# bootloader1.net
KiCad netlist of a schematic drawn in EAGLE
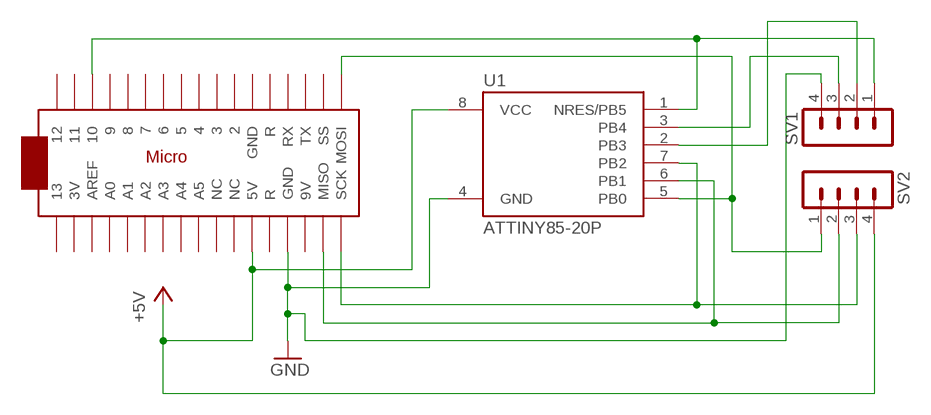
[diagram p0: schematic, sheet 1]

(export (version "E")
  (design (tool "Eeschema 10.0.6"))
  (components
    (comp (ref "SV1")
      (value "PINHEAD-MA04-1")
      (footprint "eagle-import:PINHEAD-MA04-1")
      (libsource (lib "eagle-import") (part "PINHEAD-MA04-1"))
    )
    (comp (ref "SV2")
      (value "PINHEAD-MA04-1")
      (footprint "eagle-import:PINHEAD-MA04-1")
      (libsource (lib "eagle-import") (part "PINHEAD-MA04-1"))
    )
    (comp (ref "U$1")
      (value "ARDUINOMICRO")
      (footprint "eagle-import:ARDUINOMICRO")
      (libsource (lib "eagle-import") (part "ARDUINOMICRO"))
    )
    (comp (ref "U1")
      (value "ATTINY85-20P")
      (footprint "eagle-import:PDIP08_300MIL")
      (libsource (lib "eagle-import") (part "ATTINY85P-20"))
    )
  )
  (nets
    (net (code "1") (name "+5V") (class "Default")
      (node (ref "SV2") (pin "4") (pinfunction "4_4") (pintype "passive"))
      (node (ref "U$1") (pin "P$23") (pinfunction "5V_P$23") (pintype "bidirectional"))
      (node (ref "U1") (pin "8") (pinfunction "VCC_8") (pintype "power_in"))
    )
    (net (code "2") (name "GND") (class "Default")
      (node (ref "SV1") (pin "4") (pinfunction "4_4") (pintype "passive"))
      (node (ref "U$1") (pin "P$12") (pinfunction "GND_P$12") (pintype "bidirectional"))
      (node (ref "U1") (pin "4") (pinfunction "GND_4") (pintype "power_in"))
    )
    (net (code "3") (name "Net-(U$1-10)") (class "Default")
      (node (ref "SV1") (pin "1") (pinfunction "1_1") (pintype "passive"))
      (node (ref "U$1") (pin "P$3") (pinfunction "10_P$3") (pintype "bidirectional"))
      (node (ref "U1") (pin "1") (pinfunction "NRES/PB5_1") (pintype "bidirectional"))
    )
    (net (code "4") (name "Net-(U$1-MISO)") (class "Default")
      (node (ref "SV2") (pin "2") (pinfunction "2_2") (pintype "passive"))
      (node (ref "U$1") (pin "P$19") (pinfunction "MISO_P$19") (pintype "bidirectional"))
      (node (ref "U1") (pin "6") (pinfunction "PB1_6") (pintype "bidirectional"))
    )
    (net (code "5") (name "Net-(U$1-MOSI)") (class "Default")
      (node (ref "SV2") (pin "1") (pinfunction "1_1") (pintype "passive"))
      (node (ref "U$1") (pin "P$17") (pinfunction "MOSI_P$17") (pintype "bidirectional"))
      (node (ref "U1") (pin "5") (pinfunction "PB0_5") (pintype "bidirectional"))
    )
    (net (code "6") (name "Net-(U$1-SCK)") (class "Default")
      (node (ref "SV2") (pin "3") (pinfunction "3_3") (pintype "passive"))
      (node (ref "U$1") (pin "P$18") (pinfunction "SCK_P$18") (pintype "bidirectional"))
      (node (ref "U1") (pin "7") (pinfunction "PB2_7") (pintype "bidirectional"))
    )
    (net (code "7") (name "Net-(U1-PB3)") (class "Default")
      (node (ref "SV1") (pin "2") (pinfunction "2_2") (pintype "passive"))
      (node (ref "U1") (pin "2") (pinfunction "PB3_2") (pintype "bidirectional"))
    )
    (net (code "8") (name "Net-(U1-PB4)") (class "Default")
      (node (ref "SV1") (pin "3") (pinfunction "3_3") (pintype "passive"))
      (node (ref "U1") (pin "3") (pinfunction "PB4_3") (pintype "bidirectional"))
    )
    (net (code "9") (name "unconnected-(U$1-2-PadP$11)") (class "Default")
      (node (ref "U$1") (pin "P$11") (pinfunction "2_P$11") (pintype "bidirectional"))
    )
    (net (code "10") (name "unconnected-(U$1-3-PadP$10)") (class "Default")
      (node (ref "U$1") (pin "P$10") (pinfunction "3_P$10") (pintype "bidirectional"))
    )
    (net (code "11") (name "unconnected-(U$1-3V-PadP$33)") (class "Default")
      (node (ref "U$1") (pin "P$33") (pinfunction "3V_P$33") (pintype "bidirectional"))
    )
    (net (code "12") (name "unconnected-(U$1-4-PadP$9)") (class "Default")
      (node (ref "U$1") (pin "P$9") (pinfunction "4_P$9") (pintype "bidirectional"))
    )
    (net (code "13") (name "unconnected-(U$1-5-PadP$8)") (class "Default")
      (node (ref "U$1") (pin "P$8") (pinfunction "5_P$8") (pintype "bidirectional"))
    )
    (net (code "14") (name "unconnected-(U$1-6-PadP$7)") (class "Default")
      (node (ref "U$1") (pin "P$7") (pinfunction "6_P$7") (pintype "bidirectional"))
    )
    (net (code "15") (name "unconnected-(U$1-7-PadP$6)") (class "Default")
      (node (ref "U$1") (pin "P$6") (pinfunction "7_P$6") (pintype "bidirectional"))
    )
    (net (code "16") (name "unconnected-(U$1-8-PadP$5)") (class "Default")
      (node (ref "U$1") (pin "P$5") (pinfunction "8_P$5") (pintype "bidirectional"))
    )
    (net (code "17") (name "unconnected-(U$1-9-PadP$4)") (class "Default")
      (node (ref "U$1") (pin "P$4") (pinfunction "9_P$4") (pintype "bidirectional"))
    )
    (net (code "18") (name "unconnected-(U$1-9V-PadP$20)") (class "Default")
      (node (ref "U$1") (pin "P$20") (pinfunction "9V_P$20") (pintype "bidirectional"))
    )
    (net (code "19") (name "unconnected-(U$1-11-PadP$2)") (class "Default")
      (node (ref "U$1") (pin "P$2") (pinfunction "11_P$2") (pintype "bidirectional"))
    )
    (net (code "20") (name "unconnected-(U$1-12-PadP$1)") (class "Default")
      (node (ref "U$1") (pin "P$1") (pinfunction "12_P$1") (pintype "bidirectional"))
    )
    (net (code "21") (name "unconnected-(U$1-13-PadP$34)") (class "Default")
      (node (ref "U$1") (pin "P$34") (pinfunction "13_P$34") (pintype "bidirectional"))
    )
    (net (code "22") (name "unconnected-(U$1-A0-PadP$31)") (class "Default")
      (node (ref "U$1") (pin "P$31") (pinfunction "A0_P$31") (pintype "bidirectional"))
    )
    (net (code "23") (name "unconnected-(U$1-A1-PadP$30)") (class "Default")
      (node (ref "U$1") (pin "P$30") (pinfunction "A1_P$30") (pintype "bidirectional"))
    )
    (net (code "24") (name "unconnected-(U$1-A2-PadP$29)") (class "Default")
      (node (ref "U$1") (pin "P$29") (pinfunction "A2_P$29") (pintype "bidirectional"))
    )
    (net (code "25") (name "unconnected-(U$1-A3-PadP$28)") (class "Default")
      (node (ref "U$1") (pin "P$28") (pinfunction "A3_P$28") (pintype "bidirectional"))
    )
    (net (code "26") (name "unconnected-(U$1-A4-PadP$27)") (class "Default")
      (node (ref "U$1") (pin "P$27") (pinfunction "A4_P$27") (pintype "bidirectional"))
    )
    (net (code "27") (name "unconnected-(U$1-A5-PadP$26)") (class "Default")
      (node (ref "U$1") (pin "P$26") (pinfunction "A5_P$26") (pintype "bidirectional"))
    )
    (net (code "28") (name "unconnected-(U$1-AREF-PadP$32)") (class "Default")
      (node (ref "U$1") (pin "P$32") (pinfunction "AREF_P$32") (pintype "bidirectional"))
    )
    (net (code "29") (name "unconnected-(U$1-GND-PadP$21)") (class "Default")
      (node (ref "U$1") (pin "P$21") (pinfunction "GND_P$21") (pintype "bidirectional"))
    )
    (net (code "30") (name "unconnected-(U$1-NC-PadP$24)") (class "Default")
      (node (ref "U$1") (pin "P$24") (pinfunction "NC_P$24") (pintype "bidirectional"))
    )
    (net (code "31") (name "unconnected-(U$1-NC-PadP$25)") (class "Default")
      (node (ref "U$1") (pin "P$25") (pinfunction "NC_P$25") (pintype "bidirectional"))
    )
    (net (code "32") (name "unconnected-(U$1-R-PadP$13)") (class "Default")
      (node (ref "U$1") (pin "P$13") (pinfunction "R_P$13") (pintype "bidirectional"))
    )
    (net (code "33") (name "unconnected-(U$1-R-PadP$22)") (class "Default")
      (node (ref "U$1") (pin "P$22") (pinfunction "R_P$22") (pintype "bidirectional"))
    )
    (net (code "34") (name "unconnected-(U$1-RX-PadP$14)") (class "Default")
      (node (ref "U$1") (pin "P$14") (pinfunction "RX_P$14") (pintype "bidirectional"))
    )
    (net (code "35") (name "unconnected-(U$1-SS-PadP$16)") (class "Default")
      (node (ref "U$1") (pin "P$16") (pinfunction "SS_P$16") (pintype "bidirectional"))
    )
    (net (code "36") (name "unconnected-(U$1-TX-PadP$15)") (class "Default")
      (node (ref "U$1") (pin "P$15") (pinfunction "TX_P$15") (pintype "bidirectional"))
    )
  )
)
